# version2.net
KiCad netlist of a schematic drawn in EAGLE
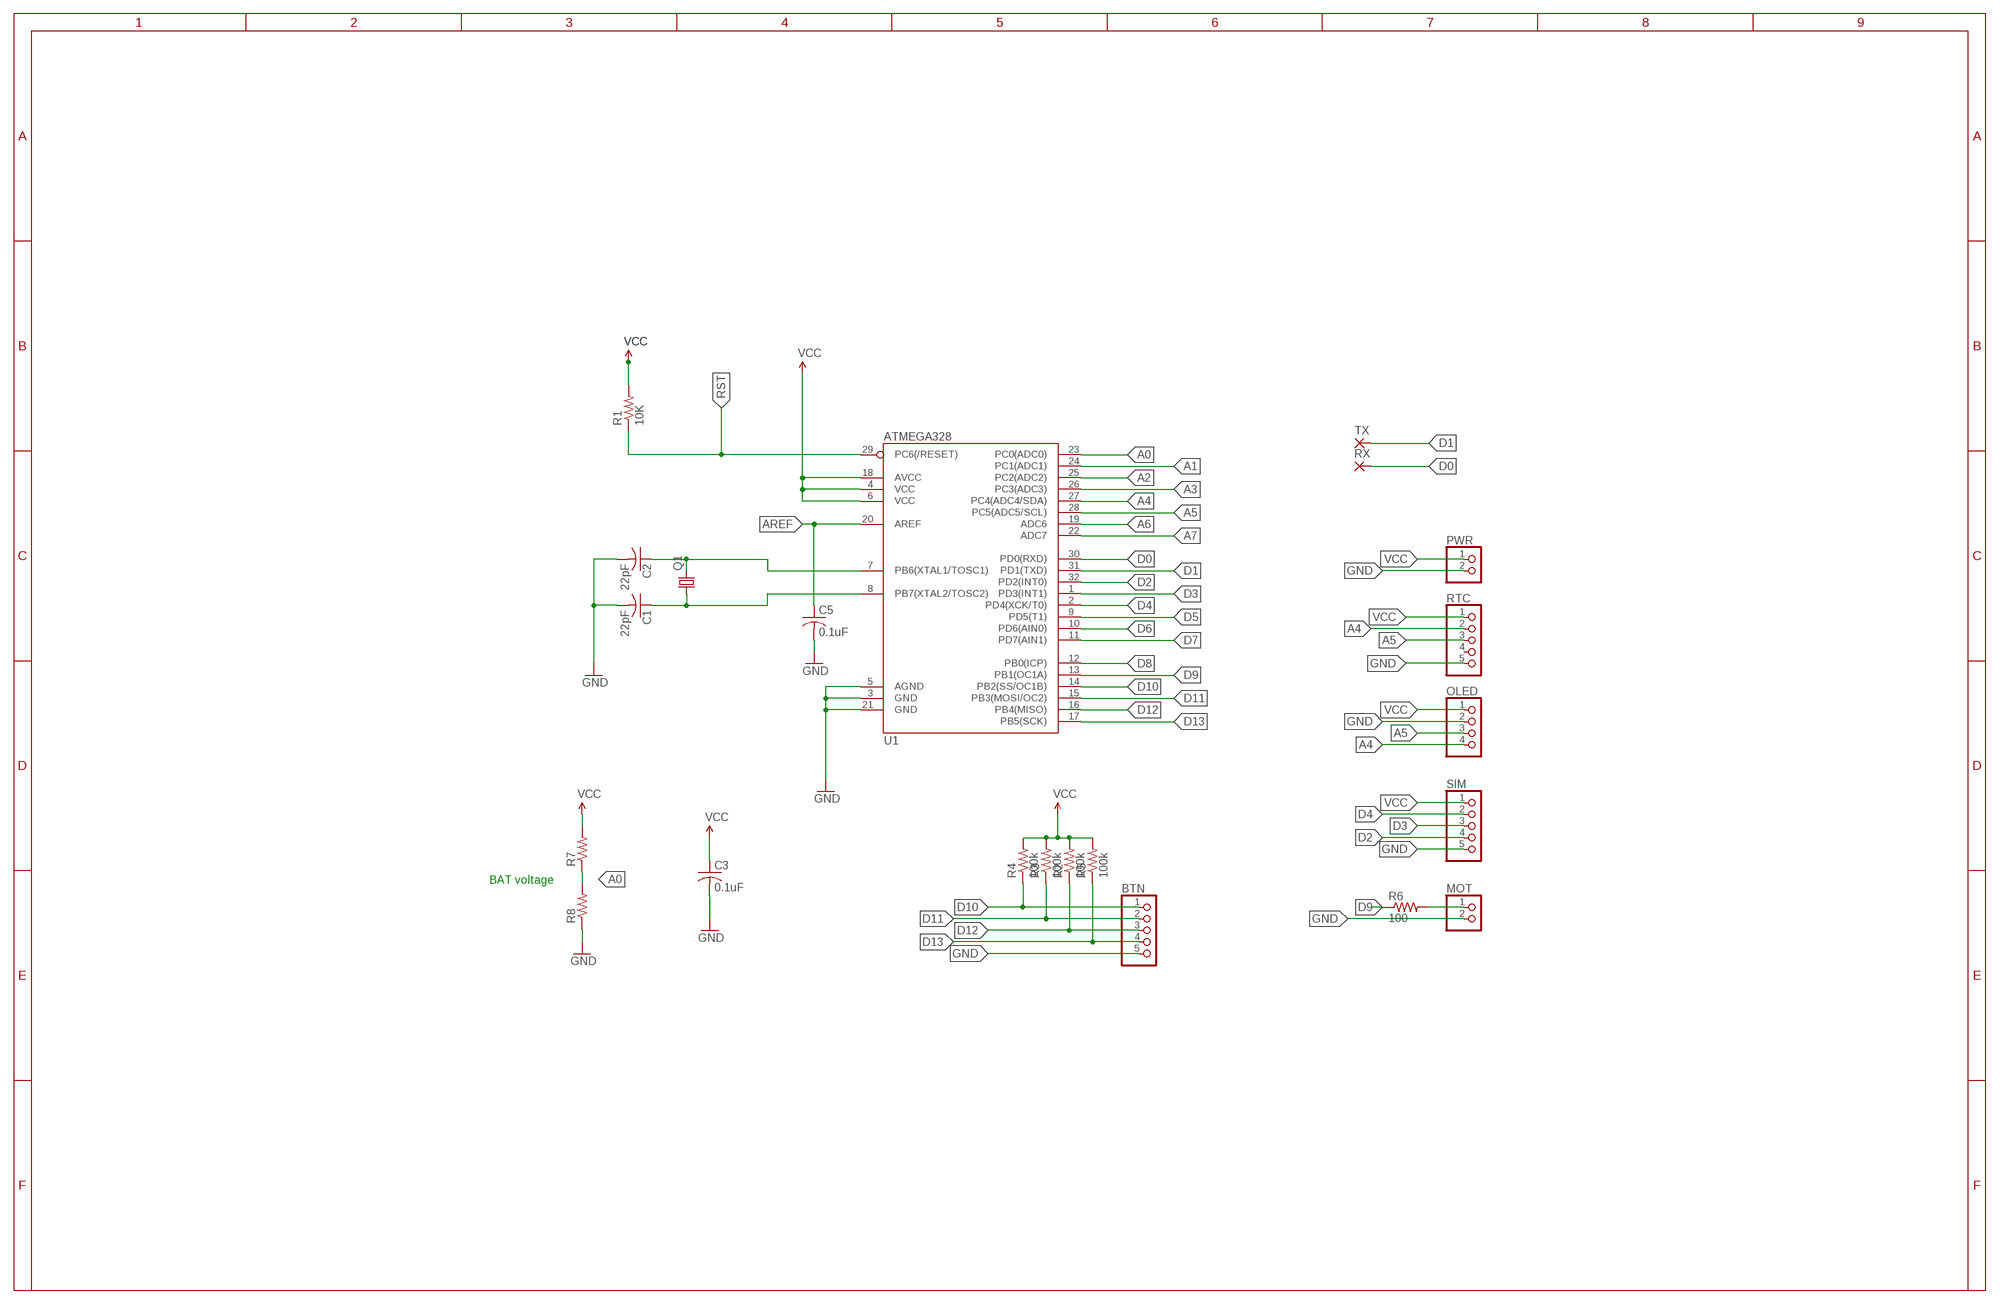
[diagram p0: schematic, sheet 1]

(export (version "E")
  (design (tool "Eeschema 10.0.6"))
  (components
    (comp (ref "BTN")
      (value "PINHD-1X5")
      (footprint "eagle-import:1X05")
      (libsource (lib "eagle-import") (part "PINHD-1X5"))
    )
    (comp (ref "C1")
      (value "22pF")
      (footprint "eagle-import:C1206")
      (libsource (lib "eagle-import") (part "C-USC1206"))
    )
    (comp (ref "C2")
      (value "22pF")
      (footprint "eagle-import:C1206")
      (libsource (lib "eagle-import") (part "C-USC1206"))
    )
    (comp (ref "C3")
      (value "0.1uF")
      (footprint "eagle-import:C0805")
      (libsource (lib "eagle-import") (part "C-USC0805"))
    )
    (comp (ref "C5")
      (value "0.1uF")
      (footprint "eagle-import:C0805")
      (libsource (lib "eagle-import") (part "C-USC0805"))
    )
    (comp (ref "MOT")
      (value "PINHD-1X2")
      (footprint "eagle-import:1X02")
      (libsource (lib "eagle-import") (part "PINHD-1X2"))
    )
    (comp (ref "OLED")
      (value "PINHD-1X4")
      (footprint "eagle-import:1X04")
      (libsource (lib "eagle-import") (part "PINHD-1X4"))
    )
    (comp (ref "PWR")
      (value "PINHD-1X2")
      (footprint "eagle-import:1X02")
      (libsource (lib "eagle-import") (part "PINHD-1X2"))
    )
    (comp (ref "Q1")
      (value "CRYSTALHC18U-V")
      (footprint "eagle-import:HC18U-V")
      (libsource (lib "eagle-import") (part "CRYSTALHC18U-V"))
    )
    (comp (ref "R1")
      (value "10K")
      (footprint "eagle-import:R0805")
      (libsource (lib "eagle-import") (part "R-US_R0805"))
    )
    (comp (ref "R2")
      (value "100k")
      (footprint "eagle-import:R0805")
      (libsource (lib "eagle-import") (part "R-US_R0805"))
    )
    (comp (ref "R3")
      (value "100k")
      (footprint "eagle-import:R0805")
      (libsource (lib "eagle-import") (part "R-US_R0805"))
    )
    (comp (ref "R4")
      (value "100k")
      (footprint "eagle-import:R0805")
      (libsource (lib "eagle-import") (part "R-US_R0805"))
    )
    (comp (ref "R5")
      (value "100k")
      (footprint "eagle-import:R0805")
      (libsource (lib "eagle-import") (part "R-US_R0805"))
    )
    (comp (ref "R6")
      (value "100")
      (footprint "eagle-import:R0805")
      (libsource (lib "eagle-import") (part "R-US_R0805"))
    )
    (comp (ref "R7")
      (value "R-US_R0805")
      (footprint "eagle-import:R0805")
      (libsource (lib "eagle-import") (part "R-US_R0805"))
    )
    (comp (ref "R8")
      (value "R-US_R0805")
      (footprint "eagle-import:R0805")
      (libsource (lib "eagle-import") (part "R-US_R0805"))
    )
    (comp (ref "RTC")
      (value "PINHD-1X5")
      (footprint "eagle-import:1X05")
      (libsource (lib "eagle-import") (part "PINHD-1X5"))
    )
    (comp (ref "RX")
      (value "SMD2")
      (footprint "eagle-import:SMD1,27-2,54")
      (libsource (lib "eagle-import") (part "SMD2"))
    )
    (comp (ref "SIM")
      (value "PINHD-1X5")
      (footprint "eagle-import:1X05")
      (libsource (lib "eagle-import") (part "PINHD-1X5"))
    )
    (comp (ref "TX")
      (value "SMD2")
      (footprint "eagle-import:SMD1,27-2,54")
      (libsource (lib "eagle-import") (part "SMD2"))
    )
    (comp (ref "U1")
      (value "ATMEGA328")
      (footprint "eagle-import:TQFP32-08")
      (libsource (lib "eagle-import") (part "ATMEGA328"))
    )
  )
  (nets
    (net (code "1") (name "A0") (class "Default")
      (node (ref "R7") (pin "1") (pinfunction "1_1") (pintype "passive"))
      (node (ref "R8") (pin "2") (pinfunction "2_2") (pintype "passive"))
      (node (ref "U1") (pin "23") (pinfunction "PC0(ADC0)_23") (pintype "bidirectional"))
    )
    (net (code "2") (name "A1") (class "Default")
      (node (ref "U1") (pin "24") (pinfunction "PC1(ADC1)_24") (pintype "bidirectional"))
    )
    (net (code "3") (name "A2") (class "Default")
      (node (ref "U1") (pin "25") (pinfunction "PC2(ADC2)_25") (pintype "bidirectional"))
    )
    (net (code "4") (name "A3") (class "Default")
      (node (ref "U1") (pin "26") (pinfunction "PC3(ADC3)_26") (pintype "bidirectional"))
    )
    (net (code "5") (name "A4") (class "Default")
      (node (ref "OLED") (pin "4") (pinfunction "4_4") (pintype "passive"))
      (node (ref "RTC") (pin "2") (pinfunction "2_2") (pintype "passive"))
      (node (ref "U1") (pin "27") (pinfunction "PC4(ADC4/SDA)_27") (pintype "bidirectional"))
    )
    (net (code "6") (name "A5") (class "Default")
      (node (ref "OLED") (pin "3") (pinfunction "3_3") (pintype "passive"))
      (node (ref "RTC") (pin "3") (pinfunction "3_3") (pintype "passive"))
      (node (ref "U1") (pin "28") (pinfunction "PC5(ADC5/SCL)_28") (pintype "bidirectional"))
    )
    (net (code "7") (name "A6") (class "Default")
      (node (ref "U1") (pin "19") (pinfunction "ADC6_19") (pintype "bidirectional"))
    )
    (net (code "8") (name "A7") (class "Default")
      (node (ref "U1") (pin "22") (pinfunction "ADC7_22") (pintype "bidirectional"))
    )
    (net (code "9") (name "AREF") (class "Default")
      (node (ref "C5") (pin "1") (pinfunction "1_1") (pintype "passive"))
      (node (ref "U1") (pin "20") (pinfunction "AREF_20") (pintype "bidirectional"))
    )
    (net (code "10") (name "D0") (class "Default")
      (node (ref "RX") (pin "1") (pinfunction "P_1") (pintype "passive"))
      (node (ref "U1") (pin "30") (pinfunction "PD0(RXD)_30") (pintype "bidirectional"))
    )
    (net (code "11") (name "D1") (class "Default")
      (node (ref "TX") (pin "1") (pinfunction "P_1") (pintype "passive"))
      (node (ref "U1") (pin "31") (pinfunction "PD1(TXD)_31") (pintype "bidirectional"))
    )
    (net (code "12") (name "D2") (class "Default")
      (node (ref "SIM") (pin "4") (pinfunction "4_4") (pintype "passive"))
      (node (ref "U1") (pin "32") (pinfunction "PD2(INT0)_32") (pintype "bidirectional"))
    )
    (net (code "13") (name "D3") (class "Default")
      (node (ref "SIM") (pin "3") (pinfunction "3_3") (pintype "passive"))
      (node (ref "U1") (pin "1") (pinfunction "PD3(INT1)_1") (pintype "bidirectional"))
    )
    (net (code "14") (name "D4") (class "Default")
      (node (ref "SIM") (pin "2") (pinfunction "2_2") (pintype "passive"))
      (node (ref "U1") (pin "2") (pinfunction "PD4(XCK/T0)_2") (pintype "bidirectional"))
    )
    (net (code "15") (name "D5") (class "Default")
      (node (ref "U1") (pin "9") (pinfunction "PD5(T1)_9") (pintype "bidirectional"))
    )
    (net (code "16") (name "D6") (class "Default")
      (node (ref "U1") (pin "10") (pinfunction "PD6(AIN0)_10") (pintype "bidirectional"))
    )
    (net (code "17") (name "D7") (class "Default")
      (node (ref "U1") (pin "11") (pinfunction "PD7(AIN1)_11") (pintype "bidirectional"))
    )
    (net (code "18") (name "D8") (class "Default")
      (node (ref "U1") (pin "12") (pinfunction "PB0(ICP)_12") (pintype "bidirectional"))
    )
    (net (code "19") (name "D9") (class "Default")
      (node (ref "R6") (pin "1") (pinfunction "1_1") (pintype "passive"))
      (node (ref "U1") (pin "13") (pinfunction "PB1(OC1A)_13") (pintype "bidirectional"))
    )
    (net (code "20") (name "D10") (class "Default")
      (node (ref "BTN") (pin "1") (pinfunction "1_1") (pintype "passive"))
      (node (ref "R4") (pin "1") (pinfunction "1_1") (pintype "passive"))
      (node (ref "U1") (pin "14") (pinfunction "PB2(SS/OC1B)_14") (pintype "bidirectional"))
    )
    (net (code "21") (name "D11") (class "Default")
      (node (ref "BTN") (pin "2") (pinfunction "2_2") (pintype "passive"))
      (node (ref "R3") (pin "1") (pinfunction "1_1") (pintype "passive"))
      (node (ref "U1") (pin "15") (pinfunction "PB3(MOSI/OC2)_15") (pintype "bidirectional"))
    )
    (net (code "22") (name "D12") (class "Default")
      (node (ref "BTN") (pin "3") (pinfunction "3_3") (pintype "passive"))
      (node (ref "R2") (pin "1") (pinfunction "1_1") (pintype "passive"))
      (node (ref "U1") (pin "16") (pinfunction "PB4(MISO)_16") (pintype "bidirectional"))
    )
    (net (code "23") (name "D13") (class "Default")
      (node (ref "BTN") (pin "4") (pinfunction "4_4") (pintype "passive"))
      (node (ref "R5") (pin "1") (pinfunction "1_1") (pintype "passive"))
      (node (ref "U1") (pin "17") (pinfunction "PB5(SCK)_17") (pintype "bidirectional"))
    )
    (net (code "24") (name "GND") (class "Default")
      (node (ref "BTN") (pin "5") (pinfunction "5_5") (pintype "passive"))
      (node (ref "C1") (pin "2") (pinfunction "2_2") (pintype "passive"))
      (node (ref "C2") (pin "2") (pinfunction "2_2") (pintype "passive"))
      (node (ref "C3") (pin "2") (pinfunction "2_2") (pintype "passive"))
      (node (ref "C5") (pin "2") (pinfunction "2_2") (pintype "passive"))
      (node (ref "MOT") (pin "2") (pinfunction "2_2") (pintype "passive"))
      (node (ref "OLED") (pin "2") (pinfunction "2_2") (pintype "passive"))
      (node (ref "PWR") (pin "2") (pinfunction "2_2") (pintype "passive"))
      (node (ref "R8") (pin "1") (pinfunction "1_1") (pintype "passive"))
      (node (ref "RTC") (pin "5") (pinfunction "5_5") (pintype "passive"))
      (node (ref "SIM") (pin "5") (pinfunction "5_5") (pintype "passive"))
      (node (ref "U1") (pin "21") (pinfunction "GND_21") (pintype "bidirectional"))
      (node (ref "U1") (pin "3") (pinfunction "GND_3") (pintype "bidirectional"))
      (node (ref "U1") (pin "5") (pinfunction "AGND_5") (pintype "bidirectional"))
    )
    (net (code "25") (name "Net-(MOT-Pad1)") (class "Default")
      (node (ref "MOT") (pin "1") (pinfunction "1_1") (pintype "passive"))
      (node (ref "R6") (pin "2") (pinfunction "2_2") (pintype "passive"))
    )
    (net (code "26") (name "Net-(U1-PB6(XTAL1{slash}TOSC1))") (class "Default")
      (node (ref "C2") (pin "1") (pinfunction "1_1") (pintype "passive"))
      (node (ref "Q1") (pin "2") (pinfunction "2_2") (pintype "passive"))
      (node (ref "U1") (pin "7") (pinfunction "PB6(XTAL1/TOSC1)_7") (pintype "bidirectional"))
    )
    (net (code "27") (name "Net-(U1-PB7(XTAL2{slash}TOSC2))") (class "Default")
      (node (ref "C1") (pin "1") (pinfunction "1_1") (pintype "passive"))
      (node (ref "Q1") (pin "1") (pinfunction "1_1") (pintype "passive"))
      (node (ref "U1") (pin "8") (pinfunction "PB7(XTAL2/TOSC2)_8") (pintype "bidirectional"))
    )
    (net (code "28") (name "RST") (class "Default")
      (node (ref "R1") (pin "1") (pinfunction "1_1") (pintype "passive"))
      (node (ref "U1") (pin "29") (pinfunction "PC6(/RESET)_29") (pintype "bidirectional"))
    )
    (net (code "29") (name "VCC") (class "Default")
      (node (ref "C3") (pin "1") (pinfunction "1_1") (pintype "passive"))
      (node (ref "OLED") (pin "1") (pinfunction "1_1") (pintype "passive"))
      (node (ref "PWR") (pin "1") (pinfunction "1_1") (pintype "passive"))
      (node (ref "R1") (pin "2") (pinfunction "2_2") (pintype "passive"))
      (node (ref "R2") (pin "2") (pinfunction "2_2") (pintype "passive"))
      (node (ref "R3") (pin "2") (pinfunction "2_2") (pintype "passive"))
      (node (ref "R4") (pin "2") (pinfunction "2_2") (pintype "passive"))
      (node (ref "R5") (pin "2") (pinfunction "2_2") (pintype "passive"))
      (node (ref "R7") (pin "2") (pinfunction "2_2") (pintype "passive"))
      (node (ref "RTC") (pin "1") (pinfunction "1_1") (pintype "passive"))
      (node (ref "SIM") (pin "1") (pinfunction "1_1") (pintype "passive"))
      (node (ref "U1") (pin "18") (pinfunction "AVCC_18") (pintype "bidirectional"))
      (node (ref "U1") (pin "4") (pinfunction "VCC_4") (pintype "bidirectional"))
      (node (ref "U1") (pin "6") (pinfunction "VCC_6") (pintype "bidirectional"))
    )
    (net (code "30") (name "unconnected-(RTC-Pad4)") (class "Default")
      (node (ref "RTC") (pin "4") (pinfunction "4_4") (pintype "passive"))
    )
  )
)
